# BDC_Motor_V01_220805.net
KiCad netlist of a schematic drawn in Altium Designer
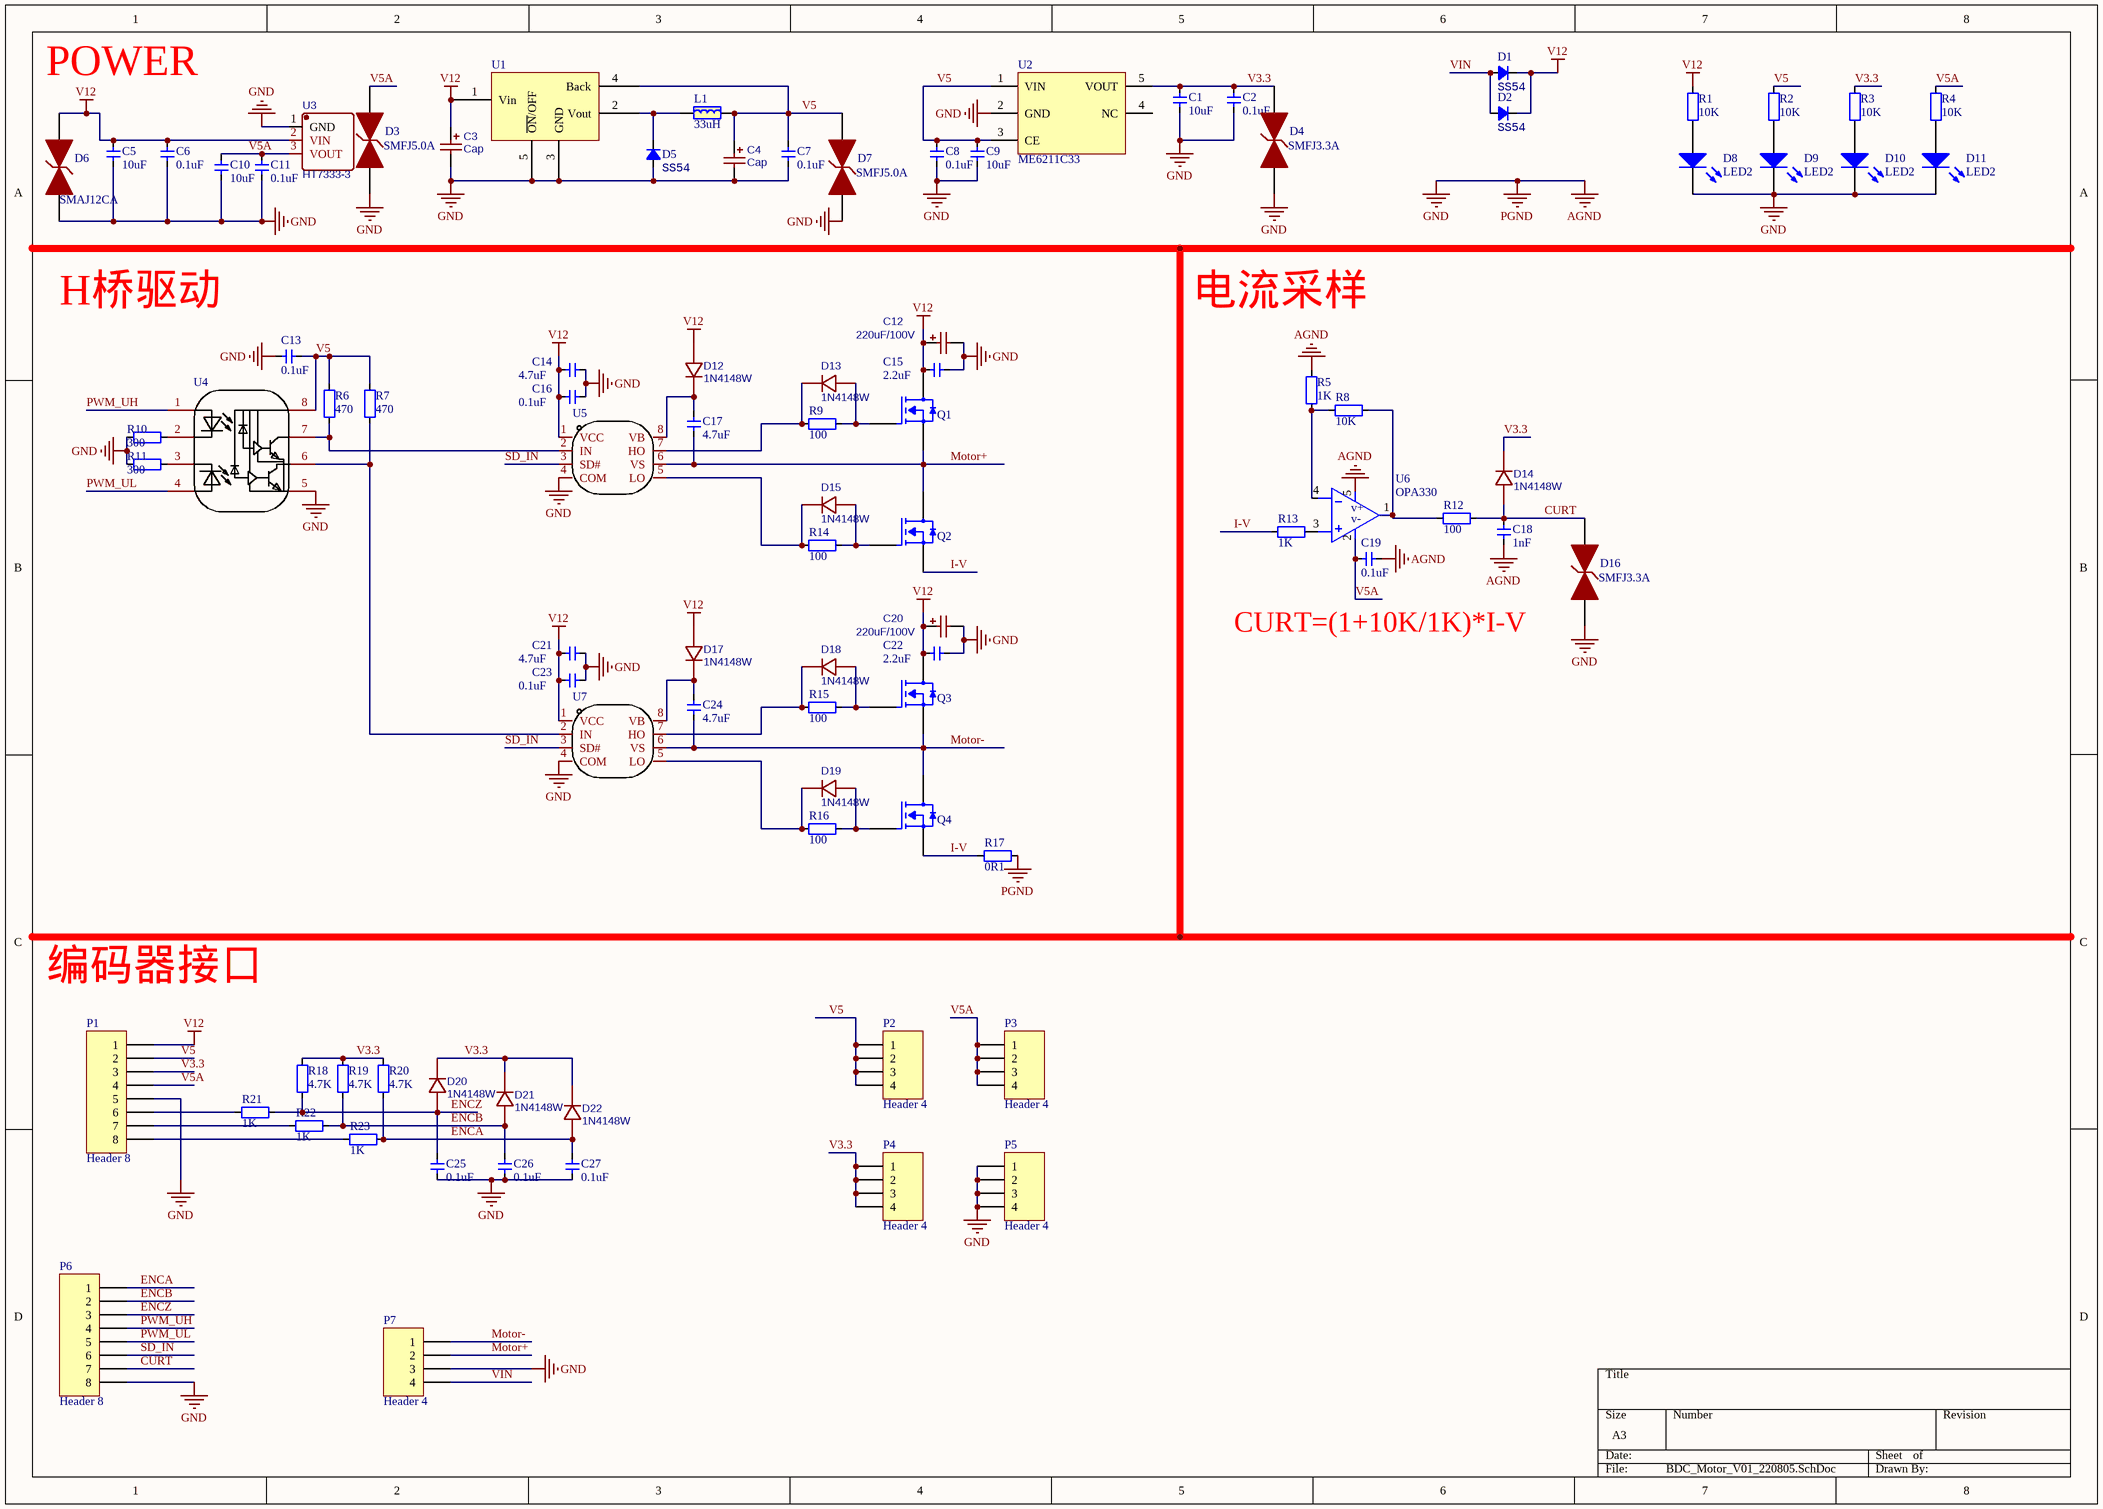
[diagram p0: BDC_Motor_V01_220805.SchDoc]

(export (version "E")
  (design (tool "Eeschema 10.0.6"))
  (components
    (comp (ref "C1")
      (value "10uF")
      (footprint "C0603")
      (description "Capacitor")
      (libsource (lib "ZtYADLib") (part "电容"))
    )
    (comp (ref "C2")
      (value "0.1uF")
      (footprint "C0603")
      (description "Capacitor")
      (libsource (lib "ZtYADLib") (part "电容"))
    )
    (comp (ref "C3")
      (value "Cap")
      (footprint "CAP-SMD_L7.3-W4.3")
      (fields
        (field (name "BOM_MANUFACTURER PART") "CA45-A-16V-10uF-K")
        (field (name "BOM_SUPPLIER PART") "C128254")
        (field (name "CONTRIBUTOR") "LCSC")
      )
      (libsource (lib "ZtYADLib") (part "极性电容"))
    )
    (comp (ref "C4")
      (value "Cap")
      (footprint "CAP-SMD_L3.5-W2.8")
      (fields
        (field (name "BOM_MANUFACTURER PART") "CA45-A-16V-10uF-K")
        (field (name "BOM_SUPPLIER PART") "C128254")
        (field (name "CONTRIBUTOR") "LCSC")
      )
      (libsource (lib "ZtYADLib") (part "极性电容"))
    )
    (comp (ref "C5")
      (value "10uF")
      (footprint "C0603")
      (description "Capacitor")
      (libsource (lib "ZtYADLib") (part "电容"))
    )
    (comp (ref "C6")
      (value "0.1uF")
      (footprint "C0603")
      (description "Capacitor")
      (libsource (lib "ZtYADLib") (part "电容"))
    )
    (comp (ref "C7")
      (value "0.1uF")
      (footprint "C0603")
      (description "Capacitor")
      (libsource (lib "ZtYADLib") (part "电容"))
    )
    (comp (ref "C8")
      (value "0.1uF")
      (footprint "C0603")
      (description "Capacitor")
      (libsource (lib "ZtYADLib") (part "电容"))
    )
    (comp (ref "C9")
      (value "10uF")
      (footprint "C0603")
      (description "Capacitor")
      (libsource (lib "ZtYADLib") (part "电容"))
    )
    (comp (ref "C10")
      (value "10uF")
      (footprint "C0603")
      (description "Capacitor")
      (libsource (lib "ZtYADLib") (part "电容"))
    )
    (comp (ref "C11")
      (value "0.1uF")
      (footprint "C0603")
      (description "Capacitor")
      (libsource (lib "ZtYADLib") (part "电容"))
    )
    (comp (ref "C12")
      (value "220uF/100V")
      (footprint "CAP-TH_BD13.0-P5.00-D1.2-FD")
      (fields
        (field (name "BOM_MANUFACTURER PART") "CA45-A-16V-10uF-K")
        (field (name "BOM_SUPPLIER PART") "C128254")
        (field (name "CONTRIBUTOR") "LCSC")
      )
      (libsource (lib "ZtYADLib") (part "极性电容"))
    )
    (comp (ref "C13")
      (value "0.1uF")
      (footprint "C0603")
      (description "Capacitor")
      (libsource (lib "ZtYADLib") (part "电容"))
    )
    (comp (ref "C14")
      (value "4.7uF")
      (footprint "C0603")
      (description "Capacitor")
      (libsource (lib "ZtYADLib") (part "电容"))
    )
    (comp (ref "C15")
      (value "2.2uF")
      (footprint "C0603")
      (description "Capacitor")
      (libsource (lib "ZtYADLib") (part "电容"))
    )
    (comp (ref "C16")
      (value "0.1uF")
      (footprint "C0603")
      (description "Capacitor")
      (libsource (lib "ZtYADLib") (part "电容"))
    )
    (comp (ref "C17")
      (value "4.7uF")
      (footprint "C0603")
      (description "Capacitor")
      (libsource (lib "ZtYADLib") (part "电容"))
    )
    (comp (ref "C18")
      (value "1nF")
      (footprint "C0603")
      (description "Capacitor")
      (libsource (lib "ZtYADLib") (part "电容"))
    )
    (comp (ref "C19")
      (value "0.1uF")
      (footprint "C0603")
      (description "Capacitor")
      (libsource (lib "ZtYADLib") (part "电容"))
    )
    (comp (ref "C20")
      (value "220uF/100V")
      (footprint "CAP-TH_BD13.0-P5.00-D1.2-FD")
      (fields
        (field (name "BOM_MANUFACTURER PART") "CA45-A-16V-10uF-K")
        (field (name "BOM_SUPPLIER PART") "C128254")
        (field (name "CONTRIBUTOR") "LCSC")
      )
      (libsource (lib "ZtYADLib") (part "极性电容"))
    )
    (comp (ref "C21")
      (value "4.7uF")
      (footprint "C0603")
      (description "Capacitor")
      (libsource (lib "ZtYADLib") (part "电容"))
    )
    (comp (ref "C22")
      (value "2.2uF")
      (footprint "C0603")
      (description "Capacitor")
      (libsource (lib "ZtYADLib") (part "电容"))
    )
    (comp (ref "C23")
      (value "0.1uF")
      (footprint "C0603")
      (description "Capacitor")
      (libsource (lib "ZtYADLib") (part "电容"))
    )
    (comp (ref "C24")
      (value "4.7uF")
      (footprint "C0603")
      (description "Capacitor")
      (libsource (lib "ZtYADLib") (part "电容"))
    )
    (comp (ref "C25")
      (value "0.1uF")
      (footprint "C0603")
      (description "Capacitor")
      (libsource (lib "ZtYADLib") (part "电容"))
    )
    (comp (ref "C26")
      (value "0.1uF")
      (footprint "C0603")
      (description "Capacitor")
      (libsource (lib "ZtYADLib") (part "电容"))
    )
    (comp (ref "C27")
      (value "0.1uF")
      (footprint "C0603")
      (description "Capacitor")
      (libsource (lib "ZtYADLib") (part "电容"))
    )
    (comp (ref "D1")
      (value "SS54")
      (footprint "DO-214AC")
      (description "Diode")
      (libsource (lib "ZtYADLib") (part "Diode_SMA"))
    )
    (comp (ref "D2")
      (value "SS54")
      (footprint "DO-214AC")
      (description "Diode")
      (libsource (lib "ZtYADLib") (part "Diode_SMA"))
    )
    (comp (ref "D3")
      (value "SMFJ5.0A")
      (footprint "SMBJ-CA_MFG")
      (libsource (lib "ZtYADLib") (part "SMBJ28CA"))
    )
    (comp (ref "D4")
      (value "SMFJ3.3A")
      (footprint "SMBJ-CA_MFG")
      (libsource (lib "ZtYADLib") (part "SMBJ28CA"))
    )
    (comp (ref "D5")
      (value "SS54")
      (footprint "DO-214AC")
      (description "Diode")
      (libsource (lib "ZtYADLib") (part "Diode_SMA"))
    )
    (comp (ref "D6")
      (value "SMAJ12CA")
      (footprint "SMBJ-CA_MFG")
      (libsource (lib "ZtYADLib") (part "SMBJ28CA"))
    )
    (comp (ref "D7")
      (value "SMFJ5.0A")
      (footprint "SMBJ-CA_MFG")
      (libsource (lib "ZtYADLib") (part "SMBJ28CA"))
    )
    (comp (ref "D8")
      (value "LED2")
      (footprint "SOD-123FL_L2.6-W1.6-LS3.4-RD")
      (description "Typical RED, GREEN, YELLOW, AMBER GaAs LED")
      (fields (field (name "PUBLISHER") "Altium Limited"))
      (libsource (lib "ZtYADLib") (part "LED2"))
    )
    (comp (ref "D9")
      (value "LED2")
      (footprint "SOD-123FL_L2.6-W1.6-LS3.4-RD")
      (description "Typical RED, GREEN, YELLOW, AMBER GaAs LED")
      (fields (field (name "PUBLISHER") "Altium Limited"))
      (libsource (lib "ZtYADLib") (part "LED2"))
    )
    (comp (ref "D10")
      (value "LED2")
      (footprint "SOD-123FL_L2.6-W1.6-LS3.4-RD")
      (description "Typical RED, GREEN, YELLOW, AMBER GaAs LED")
      (fields (field (name "PUBLISHER") "Altium Limited"))
      (libsource (lib "ZtYADLib") (part "LED2"))
    )
    (comp (ref "D11")
      (value "LED2")
      (footprint "SOD-123FL_L2.6-W1.6-LS3.4-RD")
      (description "Typical RED, GREEN, YELLOW, AMBER GaAs LED")
      (fields (field (name "PUBLISHER") "Altium Limited"))
      (libsource (lib "ZtYADLib") (part "LED2"))
    )
    (comp (ref "D12")
      (value "1N4148W")
      (footprint "SOD-123FL_L2.6-W1.6-LS3.4-RD")
      (fields (field (name "BOM_SUPPLIER PART") "C129216") (field (name "CONTRIBUTOR") "LCEDA_Lib"))
      (libsource (lib "ZtYADLib") (part "1N4148W"))
    )
    (comp (ref "D13")
      (value "1N4148W")
      (footprint "SOD-123FL_L2.6-W1.6-LS3.4-RD")
      (fields (field (name "BOM_SUPPLIER PART") "C129216") (field (name "CONTRIBUTOR") "LCEDA_Lib"))
      (libsource (lib "ZtYADLib") (part "1N4148W"))
    )
    (comp (ref "D14")
      (value "1N4148W")
      (footprint "SOD-123FL_L2.6-W1.6-LS3.4-RD")
      (fields (field (name "BOM_SUPPLIER PART") "C129216") (field (name "CONTRIBUTOR") "LCEDA_Lib"))
      (libsource (lib "ZtYADLib") (part "1N4148W"))
    )
    (comp (ref "D15")
      (value "1N4148W")
      (footprint "SOD-123FL_L2.6-W1.6-LS3.4-RD")
      (fields (field (name "BOM_SUPPLIER PART") "C129216") (field (name "CONTRIBUTOR") "LCEDA_Lib"))
      (libsource (lib "ZtYADLib") (part "1N4148W"))
    )
    (comp (ref "D16")
      (value "SMFJ3.3A")
      (footprint "SMBJ-CA_MFG")
      (libsource (lib "ZtYADLib") (part "SMBJ28CA"))
    )
    (comp (ref "D17")
      (value "1N4148W")
      (footprint "SOD-123FL_L2.6-W1.6-LS3.4-RD")
      (fields (field (name "BOM_SUPPLIER PART") "C129216") (field (name "CONTRIBUTOR") "LCEDA_Lib"))
      (libsource (lib "ZtYADLib") (part "1N4148W"))
    )
    (comp (ref "D18")
      (value "1N4148W")
      (footprint "SOD-123FL_L2.6-W1.6-LS3.4-RD")
      (fields (field (name "BOM_SUPPLIER PART") "C129216") (field (name "CONTRIBUTOR") "LCEDA_Lib"))
      (libsource (lib "ZtYADLib") (part "1N4148W"))
    )
    (comp (ref "D19")
      (value "1N4148W")
      (footprint "SOD-123FL_L2.6-W1.6-LS3.4-RD")
      (fields (field (name "BOM_SUPPLIER PART") "C129216") (field (name "CONTRIBUTOR") "LCEDA_Lib"))
      (libsource (lib "ZtYADLib") (part "1N4148W"))
    )
    (comp (ref "D20")
      (value "1N4148W")
      (footprint "SOD-123FL_L2.6-W1.6-LS3.4-RD")
      (fields (field (name "BOM_SUPPLIER PART") "C129216") (field (name "CONTRIBUTOR") "LCEDA_Lib"))
      (libsource (lib "ZtYADLib") (part "1N4148W"))
    )
    (comp (ref "D21")
      (value "1N4148W")
      (footprint "SOD-123FL_L2.6-W1.6-LS3.4-RD")
      (fields (field (name "BOM_SUPPLIER PART") "C129216") (field (name "CONTRIBUTOR") "LCEDA_Lib"))
      (libsource (lib "ZtYADLib") (part "1N4148W"))
    )
    (comp (ref "D22")
      (value "1N4148W")
      (footprint "SOD-123FL_L2.6-W1.6-LS3.4-RD")
      (fields (field (name "BOM_SUPPLIER PART") "C129216") (field (name "CONTRIBUTOR") "LCEDA_Lib"))
      (libsource (lib "ZtYADLib") (part "1N4148W"))
    )
    (comp (ref "L1")
      (value "33uH")
      (footprint "IND-SMD_L7.3-W7.3_YPRH0704")
      (libsource (lib "ZtYADLib") (part "电感"))
    )
    (comp (ref "P1")
      (value "Header 8")
      (footprint "CONN-TH_8P-P2.50_ZH-8A")
      (description "Header, 8-Pin")
      (fields (field (name "PUBLISHER") "Altium Limited"))
      (libsource (lib "Miscellaneous Connectors") (part "Header 8"))
    )
    (comp (ref "P2")
      (value "Header 4")
      (footprint "HDR1X4")
      (description "Header, 4-Pin")
      (fields (field (name "PUBLISHER") "Altium Limited"))
      (libsource (lib "Miscellaneous Connectors") (part "Header 4"))
    )
    (comp (ref "P3")
      (value "Header 4")
      (footprint "HDR1X4")
      (description "Header, 4-Pin")
      (fields (field (name "PUBLISHER") "Altium Limited"))
      (libsource (lib "Miscellaneous Connectors") (part "Header 4"))
    )
    (comp (ref "P4")
      (value "Header 4")
      (footprint "HDR1X4")
      (description "Header, 4-Pin")
      (fields (field (name "PUBLISHER") "Altium Limited"))
      (libsource (lib "Miscellaneous Connectors") (part "Header 4"))
    )
    (comp (ref "P5")
      (value "Header 4")
      (footprint "HDR1X4")
      (description "Header, 4-Pin")
      (fields (field (name "PUBLISHER") "Altium Limited"))
      (libsource (lib "Miscellaneous Connectors") (part "Header 4"))
    )
    (comp (ref "P6")
      (value "Header 8")
      (footprint "HDR1X8")
      (description "Header, 8-Pin")
      (fields (field (name "PUBLISHER") "Altium Limited"))
      (libsource (lib "Miscellaneous Connectors") (part "Header 8"))
    )
    (comp (ref "P7")
      (value "Header 4")
      (footprint "CONN-TH_4P-P3.81_KF2EDGV-3.81-4P")
      (description "Header, 4-Pin")
      (fields (field (name "PUBLISHER") "Altium Limited"))
      (libsource (lib "") (part "Header 4_1"))
    )
    (comp (ref "Q1")
      (value "AO3400A")
      (footprint "SOT23-3")
      (description "N-MOS")
      (libsource (lib "ZtYADLib") (part "AO3400A"))
    )
    (comp (ref "Q2")
      (value "AO3400A")
      (footprint "SOT23-3")
      (description "N-MOS")
      (libsource (lib "ZtYADLib") (part "AO3400A"))
    )
    (comp (ref "Q3")
      (value "AO3400A")
      (footprint "SOT23-3")
      (description "N-MOS")
      (libsource (lib "ZtYADLib") (part "AO3400A"))
    )
    (comp (ref "Q4")
      (value "AO3400A")
      (footprint "SOT23-3")
      (description "N-MOS")
      (libsource (lib "ZtYADLib") (part "AO3400A"))
    )
    (comp (ref "R1")
      (value "10K")
      (footprint "R0603")
      (description "Resistor")
      (libsource (lib "") (part "电阻_1"))
    )
    (comp (ref "R2")
      (value "10K")
      (footprint "R0603")
      (description "Resistor")
      (libsource (lib "") (part "电阻_1"))
    )
    (comp (ref "R3")
      (value "10K")
      (footprint "R0603")
      (description "Resistor")
      (libsource (lib "") (part "电阻_1"))
    )
    (comp (ref "R4")
      (value "10K")
      (footprint "R0603")
      (description "Resistor")
      (libsource (lib "") (part "电阻_1"))
    )
    (comp (ref "R5")
      (value "1K")
      (footprint "R0603")
      (description "Resistor")
      (libsource (lib "") (part "电阻_1"))
    )
    (comp (ref "R6")
      (value "470")
      (footprint "R0603")
      (description "Resistor")
      (libsource (lib "") (part "电阻_3"))
    )
    (comp (ref "R7")
      (value "470")
      (footprint "R0603")
      (description "Resistor")
      (libsource (lib "") (part "电阻_3"))
    )
    (comp (ref "R8")
      (value "10K")
      (footprint "R0603")
      (description "Resistor")
      (libsource (lib "ZtYADLib") (part "电阻"))
    )
    (comp (ref "R9")
      (value "100")
      (footprint "R0603")
      (description "Resistor")
      (libsource (lib "ZtYADLib") (part "电阻"))
    )
    (comp (ref "R10")
      (value "300")
      (footprint "R0603")
      (description "Resistor")
      (libsource (lib "") (part "电阻_2"))
    )
    (comp (ref "R11")
      (value "300")
      (footprint "R0603")
      (description "Resistor")
      (libsource (lib "") (part "电阻_2"))
    )
    (comp (ref "R12")
      (value "100")
      (footprint "R0603")
      (description "Resistor")
      (libsource (lib "ZtYADLib") (part "电阻"))
    )
    (comp (ref "R13")
      (value "1K")
      (footprint "R0603")
      (description "Resistor")
      (libsource (lib "ZtYADLib") (part "电阻"))
    )
    (comp (ref "R14")
      (value "100")
      (footprint "R0603")
      (description "Resistor")
      (libsource (lib "ZtYADLib") (part "电阻"))
    )
    (comp (ref "R15")
      (value "100")
      (footprint "R0603")
      (description "Resistor")
      (libsource (lib "ZtYADLib") (part "电阻"))
    )
    (comp (ref "R16")
      (value "100")
      (footprint "R0603")
      (description "Resistor")
      (libsource (lib "ZtYADLib") (part "电阻"))
    )
    (comp (ref "R17")
      (value "0R1")
      (footprint "R1206")
      (description "Resistor")
      (libsource (lib "") (part "电阻_2"))
    )
    (comp (ref "R18")
      (value "4.7K")
      (footprint "R0603")
      (description "Resistor")
      (libsource (lib "") (part "电阻_1"))
    )
    (comp (ref "R19")
      (value "4.7K")
      (footprint "R0603")
      (description "Resistor")
      (libsource (lib "") (part "电阻_1"))
    )
    (comp (ref "R20")
      (value "4.7K")
      (footprint "R0603")
      (description "Resistor")
      (libsource (lib "") (part "电阻_1"))
    )
    (comp (ref "R21")
      (value "1K")
      (footprint "R0603")
      (description "Resistor")
      (libsource (lib "ZtYADLib") (part "电阻"))
    )
    (comp (ref "R22")
      (value "1K")
      (footprint "R0603")
      (description "Resistor")
      (libsource (lib "ZtYADLib") (part "电阻"))
    )
    (comp (ref "R23")
      (value "1K")
      (footprint "R0603")
      (description "Resistor")
      (libsource (lib "ZtYADLib") (part "电阻"))
    )
    (comp (ref "U1")
      (value "RS2596U")
      (footprint "TO-263-5_L10.2-W8.9-P1.70-LS15.2-BR")
      (libsource (lib "ZtYADLib") (part "RS2596U"))
    )
    (comp (ref "U2")
      (value "ME6211C33")
      (footprint "SOT23-5")
      (description "LDO")
      (libsource (lib "ZtYADLib") (part "ME6211C33"))
    )
    (comp (ref "U3")
      (value "HT7333-3")
      (footprint "SOT-89-3_L4.5-W2.5-P1.50-LS4.1-BR")
      (fields (field (name "BOM_SUPPLIER PART") "C84207"))
      (libsource (lib "ZtYADLib") (part "HT7333-3"))
    )
    (comp (ref "U4")
      (value "EL0631(TA)")
      (footprint "SOP-8-SMD-8_L4.9-W4.0-P1.27-LS5.9-BL")
      (libsource (lib "ZtYADLib") (part "EL0631(TA)"))
    )
    (comp (ref "U5")
      (value "IR2104STRPBF")
      (footprint "SOIC-8_L4.9-W3.9-P1.27-LS6.0-BL")
      (libsource (lib "ZtYADLib") (part "IR2104STRPBF"))
    )
    (comp (ref "U6") (value "OPA330") (footprint "SOT23-5") (libsource (lib "ZtYADLib") (part "OPA330")))
    (comp (ref "U7")
      (value "IR2104STRPBF")
      (footprint "SOIC-8_L4.9-W3.9-P1.27-LS6.0-BL")
      (libsource (lib "ZtYADLib") (part "IR2104STRPBF"))
    )
  )
  (nets
    (net (code "1") (name "/CURT") (class "Default")
      (node (ref "C18") (pin "1") (pinfunction "1_1") (pintype "passive"))
      (node (ref "D14") (pin "2") (pinfunction "2_2") (pintype "passive"))
      (node (ref "D16") (pin "2") (pinfunction "2_2") (pintype "passive"))
      (node (ref "P6") (pin "7") (pinfunction "7_7") (pintype "passive"))
      (node (ref "R12") (pin "1") (pinfunction "1_1") (pintype "passive"))
    )
    (net (code "2") (name "/ENCA") (class "Default")
      (node (ref "C27") (pin "1") (pinfunction "1_1") (pintype "passive"))
      (node (ref "D22") (pin "2") (pinfunction "2_2") (pintype "passive"))
      (node (ref "P6") (pin "1") (pinfunction "1_1") (pintype "passive"))
      (node (ref "R20") (pin "2") (pinfunction "2_2") (pintype "passive"))
      (node (ref "R23") (pin "1") (pinfunction "1_1") (pintype "passive"))
    )
    (net (code "3") (name "/ENCB") (class "Default")
      (node (ref "C26") (pin "1") (pinfunction "1_1") (pintype "passive"))
      (node (ref "D21") (pin "2") (pinfunction "2_2") (pintype "passive"))
      (node (ref "P6") (pin "2") (pinfunction "2_2") (pintype "passive"))
      (node (ref "R19") (pin "2") (pinfunction "2_2") (pintype "passive"))
      (node (ref "R22") (pin "1") (pinfunction "1_1") (pintype "passive"))
    )
    (net (code "4") (name "/ENCZ") (class "Default")
      (node (ref "C25") (pin "1") (pinfunction "1_1") (pintype "passive"))
      (node (ref "D20") (pin "2") (pinfunction "2_2") (pintype "passive"))
      (node (ref "P6") (pin "3") (pinfunction "3_3") (pintype "passive"))
      (node (ref "R18") (pin "2") (pinfunction "2_2") (pintype "passive"))
      (node (ref "R21") (pin "1") (pinfunction "1_1") (pintype "passive"))
    )
    (net (code "5") (name "/I-V") (class "Default")
      (node (ref "Q2") (pin "2") (pinfunction "S_2") (pintype "passive"))
      (node (ref "Q4") (pin "2") (pinfunction "S_2") (pintype "passive"))
      (node (ref "R13") (pin "2") (pinfunction "2_2") (pintype "passive"))
      (node (ref "R17") (pin "1") (pinfunction "1_1") (pintype "passive"))
    )
    (net (code "6") (name "/Motor+") (class "Default")
      (node (ref "C17") (pin "2") (pinfunction "2_2") (pintype "passive"))
      (node (ref "P7") (pin "2") (pinfunction "2_2") (pintype "passive"))
      (node (ref "Q1") (pin "2") (pinfunction "S_2") (pintype "passive"))
      (node (ref "Q2") (pin "3") (pinfunction "D_3") (pintype "passive"))
      (node (ref "U5") (pin "6") (pinfunction "VS_6") (pintype "passive"))
    )
    (net (code "7") (name "/Motor-") (class "Default")
      (node (ref "C24") (pin "2") (pinfunction "2_2") (pintype "passive"))
      (node (ref "P7") (pin "1") (pinfunction "1_1") (pintype "passive"))
      (node (ref "Q3") (pin "2") (pinfunction "S_2") (pintype "passive"))
      (node (ref "Q4") (pin "3") (pinfunction "D_3") (pintype "passive"))
      (node (ref "U7") (pin "6") (pinfunction "VS_6") (pintype "passive"))
    )
    (net (code "8") (name "/PWM_UH") (class "Default")
      (node (ref "P6") (pin "4") (pinfunction "4_4") (pintype "passive"))
      (node (ref "U4") (pin "1") (pinfunction "1_1") (pintype "passive"))
    )
    (net (code "9") (name "/PWM_UL") (class "Default")
      (node (ref "P6") (pin "5") (pinfunction "5_5") (pintype "passive"))
      (node (ref "U4") (pin "4") (pinfunction "4_4") (pintype "passive"))
    )
    (net (code "10") (name "/SD_IN") (class "Default")
      (node (ref "P6") (pin "6") (pinfunction "6_6") (pintype "passive"))
      (node (ref "U5") (pin "3") (pinfunction "SD#_3") (pintype "passive"))
      (node (ref "U7") (pin "3") (pinfunction "SD#_3") (pintype "passive"))
    )
    (net (code "11") (name "/V3.3") (class "Default")
      (node (ref "C1") (pin "2") (pinfunction "2_2") (pintype "passive"))
      (node (ref "C2") (pin "2") (pinfunction "2_2") (pintype "passive"))
      (node (ref "D14") (pin "1") (pinfunction "1_1") (pintype "passive"))
      (node (ref "D20") (pin "1") (pinfunction "1_1") (pintype "passive"))
      (node (ref "D21") (pin "1") (pinfunction "1_1") (pintype "passive"))
      (node (ref "D22") (pin "1") (pinfunction "1_1") (pintype "passive"))
      (node (ref "D4") (pin "2") (pinfunction "2_2") (pintype "passive"))
      (node (ref "P1") (pin "3") (pinfunction "3_3") (pintype "passive"))
      (node (ref "P4") (pin "1") (pinfunction "1_1") (pintype "passive"))
      (node (ref "P4") (pin "2") (pinfunction "2_2") (pintype "passive"))
      (node (ref "P4") (pin "3") (pinfunction "3_3") (pintype "passive"))
      (node (ref "P4") (pin "4") (pinfunction "4_4") (pintype "passive"))
      (node (ref "R18") (pin "1") (pinfunction "1_1") (pintype "passive"))
      (node (ref "R19") (pin "1") (pinfunction "1_1") (pintype "passive"))
      (node (ref "R20") (pin "1") (pinfunction "1_1") (pintype "passive"))
      (node (ref "R3") (pin "1") (pinfunction "1_1") (pintype "passive"))
      (node (ref "U2") (pin "5") (pinfunction "VOUT_5") (pintype "passive"))
    )
    (net (code "12") (name "/V5") (class "Default")
      (node (ref "C13") (pin "2") (pinfunction "2_2") (pintype "passive"))
      (node (ref "C4") (pin "1") (pinfunction "1_1") (pintype "passive"))
      (node (ref "C7") (pin "2") (pinfunction "2_2") (pintype "passive"))
      (node (ref "C8") (pin "2") (pinfunction "2_2") (pintype "passive"))
      (node (ref "C9") (pin "2") (pinfunction "2_2") (pintype "passive"))
      (node (ref "D7") (pin "2") (pinfunction "2_2") (pintype "passive"))
      (node (ref "L1") (pin "2") (pinfunction "2_2") (pintype "passive"))
      (node (ref "P1") (pin "2") (pinfunction "2_2") (pintype "passive"))
      (node (ref "P2") (pin "1") (pinfunction "1_1") (pintype "passive"))
      (node (ref "P2") (pin "2") (pinfunction "2_2") (pintype "passive"))
      (node (ref "P2") (pin "3") (pinfunction "3_3") (pintype "passive"))
      (node (ref "P2") (pin "4") (pinfunction "4_4") (pintype "passive"))
      (node (ref "R2") (pin "1") (pinfunction "1_1") (pintype "passive"))
      (node (ref "R6") (pin "2") (pinfunction "2_2") (pintype "passive"))
      (node (ref "R7") (pin "2") (pinfunction "2_2") (pintype "passive"))
      (node (ref "U1") (pin "4") (pinfunction "Back_4") (pintype "passive"))
      (node (ref "U2") (pin "1") (pinfunction "VIN_1") (pintype "passive"))
      (node (ref "U2") (pin "3") (pinfunction "CE_3") (pintype "passive"))
      (node (ref "U4") (pin "8") (pinfunction "8_8") (pintype "passive"))
    )
    (net (code "13") (name "/V5A") (class "Default")
      (node (ref "C10") (pin "2") (pinfunction "2_2") (pintype "passive"))
      (node (ref "C11") (pin "2") (pinfunction "2_2") (pintype "passive"))
      (node (ref "C19") (pin "2") (pinfunction "2_2") (pintype "passive"))
      (node (ref "D3") (pin "2") (pinfunction "2_2") (pintype "passive"))
      (node (ref "P1") (pin "4") (pinfunction "4_4") (pintype "passive"))
      (node (ref "P3") (pin "1") (pinfunction "1_1") (pintype "passive"))
      (node (ref "P3") (pin "2") (pinfunction "2_2") (pintype "passive"))
      (node (ref "P3") (pin "3") (pinfunction "3_3") (pintype "passive"))
      (node (ref "P3") (pin "4") (pinfunction "4_4") (pintype "passive"))
      (node (ref "R4") (pin "1") (pinfunction "1_1") (pintype "passive"))
      (node (ref "U3") (pin "3") (pinfunction "VOUT_3") (pintype "passive"))
      (node (ref "U6") (pin "2") (pinfunction "v-_2") (pintype "power_in"))
    )
    (net (code "14") (name "/VIN") (class "Default")
      (node (ref "D1") (pin "2") (pinfunction "A_2") (pintype "passive"))
      (node (ref "D2") (pin "2") (pinfunction "A_2") (pintype "passive"))
      (node (ref "P7") (pin "4") (pinfunction "4_4") (pintype "passive"))
    )
    (net (code "15") (name "AGND") (class "Default")
      (node (ref "C1") (pin "1") (pinfunction "1_1") (pintype "passive"))
      (node (ref "C10") (pin "1") (pinfunction "1_1") (pintype "passive"))
      (node (ref "C11") (pin "1") (pinfunction "1_1") (pintype "passive"))
      (node (ref "C12") (pin "2") (pinfunction "2_2") (pintype "passive"))
      (node (ref "C13") (pin "1") (pinfunction "1_1") (pintype "passive"))
      (node (ref "C14") (pin "1") (pinfunction "1_1") (pintype "passive"))
      (node (ref "C15") (pin "2") (pinfunction "2_2") (pintype "passive"))
      (node (ref "C16") (pin "1") (pinfunction "1_1") (pintype "passive"))
      (node (ref "C18") (pin "2") (pinfunction "2_2") (pintype "passive"))
      (node (ref "C19") (pin "1") (pinfunction "1_1") (pintype "passive"))
      (node (ref "C2") (pin "1") (pinfunction "1_1") (pintype "passive"))
      (node (ref "C20") (pin "2") (pinfunction "2_2") (pintype "passive"))
      (node (ref "C21") (pin "1") (pinfunction "1_1") (pintype "passive"))
      (node (ref "C22") (pin "2") (pinfunction "2_2") (pintype "passive"))
      (node (ref "C23") (pin "1") (pinfunction "1_1") (pintype "passive"))
      (node (ref "C25") (pin "2") (pinfunction "2_2") (pintype "passive"))
      (node (ref "C26") (pin "2") (pinfunction "2_2") (pintype "passive"))
      (node (ref "C27") (pin "2") (pinfunction "2_2") (pintype "passive"))
      (node (ref "C3") (pin "2") (pinfunction "2_2") (pintype "passive"))
      (node (ref "C4") (pin "2") (pinfunction "2_2") (pintype "passive"))
      (node (ref "C5") (pin "1") (pinfunction "1_1") (pintype "passive"))
      (node (ref "C6") (pin "1") (pinfunction "1_1") (pintype "passive"))
      (node (ref "C7") (pin "1") (pinfunction "1_1") (pintype "passive"))
      (node (ref "C8") (pin "1") (pinfunction "1_1") (pintype "passive"))
      (node (ref "C9") (pin "1") (pinfunction "1_1") (pintype "passive"))
      (node (ref "D10") (pin "1") (pinfunction "K_1") (pintype "passive"))
      (node (ref "D11") (pin "1") (pinfunction "K_1") (pintype "passive"))
      (node (ref "D16") (pin "1") (pinfunction "1_1") (pintype "passive"))
      (node (ref "D3") (pin "1") (pinfunction "1_1") (pintype "passive"))
      (node (ref "D4") (pin "1") (pinfunction "1_1") (pintype "passive"))
      (node (ref "D5") (pin "2") (pinfunction "A_2") (pintype "passive"))
      (node (ref "D6") (pin "1") (pinfunction "1_1") (pintype "passive"))
      (node (ref "D7") (pin "1") (pinfunction "1_1") (pintype "passive"))
      (node (ref "D8") (pin "1") (pinfunction "K_1") (pintype "passive"))
      (node (ref "D9") (pin "1") (pinfunction "K_1") (pintype "passive"))
      (node (ref "P1") (pin "5") (pinfunction "5_5") (pintype "passive"))
      (node (ref "P5") (pin "1") (pinfunction "1_1") (pintype "passive"))
      (node (ref "P5") (pin "2") (pinfunction "2_2") (pintype "passive"))
      (node (ref "P5") (pin "3") (pinfunction "3_3") (pintype "passive"))
      (node (ref "P5") (pin "4") (pinfunction "4_4") (pintype "passive"))
      (node (ref "P6") (pin "8") (pinfunction "8_8") (pintype "passive"))
      (node (ref "P7") (pin "3") (pinfunction "3_3") (pintype "passive"))
      (node (ref "R10") (pin "1") (pinfunction "1_1") (pintype "passive"))
      (node (ref "R11") (pin "1") (pinfunction "1_1") (pintype "passive"))
      (node (ref "R17") (pin "2") (pinfunction "2_2") (pintype "passive"))
      (node (ref "R5") (pin "1") (pinfunction "1_1") (pintype "passive"))
      (node (ref "U1") (pin "3") (pinfunction "GND_3") (pintype "passive"))
      (node (ref "U1") (pin "5") (pinfunction "~{ON}/OFF_5") (pintype "passive"))
      (node (ref "U2") (pin "2") (pinfunction "GND_2") (pintype "passive"))
      (node (ref "U3") (pin "1") (pinfunction "GND_1") (pintype "passive"))
      (node (ref "U4") (pin "5") (pinfunction "5_5") (pintype "passive"))
      (node (ref "U5") (pin "4") (pinfunction "COM_4") (pintype "passive"))
      (node (ref "U6") (pin "5") (pinfunction "v+_5") (pintype "passive"))
      (node (ref "U7") (pin "4") (pinfunction "COM_4") (pintype "passive"))
    )
    (net (code "16") (name "Net-(D5-K)") (class "Default")
      (node (ref "D5") (pin "1") (pinfunction "K_1") (pintype "passive"))
      (node (ref "L1") (pin "1") (pintype "passive"))
      (node (ref "U1") (pin "2") (pinfunction "Vout_2") (pintype "passive"))
    )
    (net (code "17") (name "Net-(D8-A)") (class "Default")
      (node (ref "D8") (pin "2") (pinfunction "A_2") (pintype "passive"))
      (node (ref "R1") (pin "2") (pinfunction "2_2") (pintype "passive"))
    )
    (net (code "18") (name "Net-(D9-A)") (class "Default")
      (node (ref "D9") (pin "2") (pinfunction "A_2") (pintype "passive"))
      (node (ref "R2") (pin "2") (pinfunction "2_2") (pintype "passive"))
    )
    (net (code "19") (name "Net-(D10-A)") (class "Default")
      (node (ref "D10") (pin "2") (pinfunction "A_2") (pintype "passive"))
      (node (ref "R3") (pin "2") (pinfunction "2_2") (pintype "passive"))
    )
    (net (code "20") (name "Net-(D11-A)") (class "Default")
      (node (ref "D11") (pin "2") (pinfunction "A_2") (pintype "passive"))
      (node (ref "R4") (pin "2") (pinfunction "2_2") (pintype "passive"))
    )
    (net (code "21") (name "Net-(P1-Pad6)") (class "Default")
      (node (ref "P1") (pin "6") (pinfunction "6_6") (pintype "passive"))
      (node (ref "R21") (pin "2") (pinfunction "2_2") (pintype "passive"))
    )
    (net (code "22") (name "Net-(P1-Pad7)") (class "Default")
      (node (ref "P1") (pin "7") (pinfunction "7_7") (pintype "passive"))
      (node (ref "R22") (pin "2") (pinfunction "2_2") (pintype "passive"))
    )
    (net (code "23") (name "Net-(P1-Pad8)") (class "Default")
      (node (ref "P1") (pin "8") (pinfunction "8_8") (pintype "passive"))
      (node (ref "R23") (pin "2") (pinfunction "2_2") (pintype "passive"))
    )
    (net (code "24") (name "Net-(Q1-G)") (class "Default")
      (node (ref "D13") (pin "2") (pinfunction "2_2") (pintype "passive"))
      (node (ref "Q1") (pin "1") (pinfunction "G_1") (pintype "passive"))
      (node (ref "R9") (pin "1") (pinfunction "1_1") (pintype "passive"))
    )
    (net (code "25") (name "Net-(Q2-G)") (class "Default")
      (node (ref "D15") (pin "2") (pinfunction "2_2") (pintype "passive"))
      (node (ref "Q2") (pin "1") (pinfunction "G_1") (pintype "passive"))
      (node (ref "R14") (pin "1") (pinfunction "1_1") (pintype "passive"))
    )
    (net (code "26") (name "Net-(Q3-G)") (class "Default")
      (node (ref "D18") (pin "2") (pinfunction "2_2") (pintype "passive"))
      (node (ref "Q3") (pin "1") (pinfunction "G_1") (pintype "passive"))
      (node (ref "R15") (pin "1") (pinfunction "1_1") (pintype "passive"))
    )
    (net (code "27") (name "Net-(Q4-G)") (class "Default")
      (node (ref "D19") (pin "2") (pinfunction "2_2") (pintype "passive"))
      (node (ref "Q4") (pin "1") (pinfunction "G_1") (pintype "passive"))
      (node (ref "R16") (pin "1") (pinfunction "1_1") (pintype "passive"))
    )
    (net (code "28") (name "Net-(R10-Pad2)") (class "Default")
      (node (ref "R10") (pin "2") (pinfunction "2_2") (pintype "passive"))
      (node (ref "U4") (pin "2") (pinfunction "2_2") (pintype "passive"))
    )
    (net (code "29") (name "Net-(R11-Pad2)") (class "Default")
      (node (ref "R11") (pin "2") (pinfunction "2_2") (pintype "passive"))
      (node (ref "U4") (pin "3") (pinfunction "3_3") (pintype "passive"))
    )
    (net (code "30") (name "Net-(U5-HO)") (class "Default")
      (node (ref "D13") (pin "1") (pinfunction "1_1") (pintype "passive"))
      (node (ref "R9") (pin "2") (pinfunction "2_2") (pintype "passive"))
      (node (ref "U5") (pin "7") (pinfunction "HO_7") (pintype "passive"))
    )
    (net (code "31") (name "Net-(U5-IN)") (class "Default")
      (node (ref "R6") (pin "1") (pinfunction "1_1") (pintype "passive"))
      (node (ref "U4") (pin "7") (pinfunction "7_7") (pintype "passive"))
      (node (ref "U5") (pin "2") (pinfunction "IN_2") (pintype "passive"))
    )
    (net (code "32") (name "Net-(U5-LO)") (class "Default")
      (node (ref "D15") (pin "1") (pinfunction "1_1") (pintype "passive"))
      (node (ref "R14") (pin "2") (pinfunction "2_2") (pintype "passive"))
      (node (ref "U5") (pin "5") (pinfunction "LO_5") (pintype "passive"))
    )
    (net (code "33") (name "Net-(U5-VB)") (class "Default")
      (node (ref "C17") (pin "1") (pinfunction "1_1") (pintype "passive"))
      (node (ref "D12") (pin "1") (pinfunction "1_1") (pintype "passive"))
      (node (ref "U5") (pin "8") (pinfunction "VB_8") (pintype "passive"))
    )
    (net (code "34") (name "Net-(U6-+)") (class "Default")
      (node (ref "R13") (pin "1") (pinfunction "1_1") (pintype "passive"))
      (node (ref "U6") (pin "3") (pinfunction "+_3") (pintype "passive"))
    )
    (net (code "35") (name "Net-(U6--)") (class "Default")
      (node (ref "R5") (pin "2") (pinfunction "2_2") (pintype "passive"))
      (node (ref "R8") (pin "2") (pinfunction "2_2") (pintype "passive"))
      (node (ref "U6") (pin "4") (pinfunction "-_4") (pintype "passive"))
    )
    (net (code "36") (name "Net-(U6-out)") (class "Default")
      (node (ref "R12") (pin "2") (pinfunction "2_2") (pintype "passive"))
      (node (ref "R8") (pin "1") (pinfunction "1_1") (pintype "passive"))
      (node (ref "U6") (pin "1") (pinfunction "out_1") (pintype "passive"))
    )
    (net (code "37") (name "Net-(U7-HO)") (class "Default")
      (node (ref "D18") (pin "1") (pinfunction "1_1") (pintype "passive"))
      (node (ref "R15") (pin "2") (pinfunction "2_2") (pintype "passive"))
      (node (ref "U7") (pin "7") (pinfunction "HO_7") (pintype "passive"))
    )
    (net (code "38") (name "Net-(U7-IN)") (class "Default")
      (node (ref "R7") (pin "1") (pinfunction "1_1") (pintype "passive"))
      (node (ref "U4") (pin "6") (pinfunction "6_6") (pintype "passive"))
      (node (ref "U7") (pin "2") (pinfunction "IN_2") (pintype "passive"))
    )
    (net (code "39") (name "Net-(U7-LO)") (class "Default")
      (node (ref "D19") (pin "1") (pinfunction "1_1") (pintype "passive"))
      (node (ref "R16") (pin "2") (pinfunction "2_2") (pintype "passive"))
      (node (ref "U7") (pin "5") (pinfunction "LO_5") (pintype "passive"))
    )
    (net (code "40") (name "Net-(U7-VB)") (class "Default")
      (node (ref "C24") (pin "1") (pinfunction "1_1") (pintype "passive"))
      (node (ref "D17") (pin "1") (pinfunction "1_1") (pintype "passive"))
      (node (ref "U7") (pin "8") (pinfunction "VB_8") (pintype "passive"))
    )
    (net (code "41") (name "V12") (class "Default")
      (node (ref "C12") (pin "1") (pinfunction "1_1") (pintype "passive"))
      (node (ref "C14") (pin "2") (pinfunction "2_2") (pintype "passive"))
      (node (ref "C15") (pin "1") (pinfunction "1_1") (pintype "passive"))
      (node (ref "C16") (pin "2") (pinfunction "2_2") (pintype "passive"))
      (node (ref "C20") (pin "1") (pinfunction "1_1") (pintype "passive"))
      (node (ref "C21") (pin "2") (pinfunction "2_2") (pintype "passive"))
      (node (ref "C22") (pin "1") (pinfunction "1_1") (pintype "passive"))
      (node (ref "C23") (pin "2") (pinfunction "2_2") (pintype "passive"))
      (node (ref "C3") (pin "1") (pinfunction "1_1") (pintype "passive"))
      (node (ref "C5") (pin "2") (pinfunction "2_2") (pintype "passive"))
      (node (ref "C6") (pin "2") (pinfunction "2_2") (pintype "passive"))
      (node (ref "D1") (pin "1") (pinfunction "K_1") (pintype "passive"))
      (node (ref "D12") (pin "2") (pinfunction "2_2") (pintype "passive"))
      (node (ref "D17") (pin "2") (pinfunction "2_2") (pintype "passive"))
      (node (ref "D2") (pin "1") (pinfunction "K_1") (pintype "passive"))
      (node (ref "D6") (pin "2") (pinfunction "2_2") (pintype "passive"))
      (node (ref "P1") (pin "1") (pinfunction "1_1") (pintype "passive"))
      (node (ref "Q1") (pin "3") (pinfunction "D_3") (pintype "passive"))
      (node (ref "Q3") (pin "3") (pinfunction "D_3") (pintype "passive"))
      (node (ref "R1") (pin "1") (pinfunction "1_1") (pintype "passive"))
      (node (ref "U1") (pin "1") (pinfunction "Vin_1") (pintype "passive"))
      (node (ref "U3") (pin "2") (pinfunction "VIN_2") (pintype "passive"))
      (node (ref "U5") (pin "1") (pinfunction "VCC_1") (pintype "passive"))
      (node (ref "U7") (pin "1") (pinfunction "VCC_1") (pintype "passive"))
    )
    (net (code "42") (name "unconnected-(U2-NC-Pad4)") (class "Default")
      (node (ref "U2") (pin "4") (pinfunction "NC_4") (pintype "passive"))
    )
  )
)
